# ESP32.net
KiCad netlist of a schematic drawn in Altium Designer
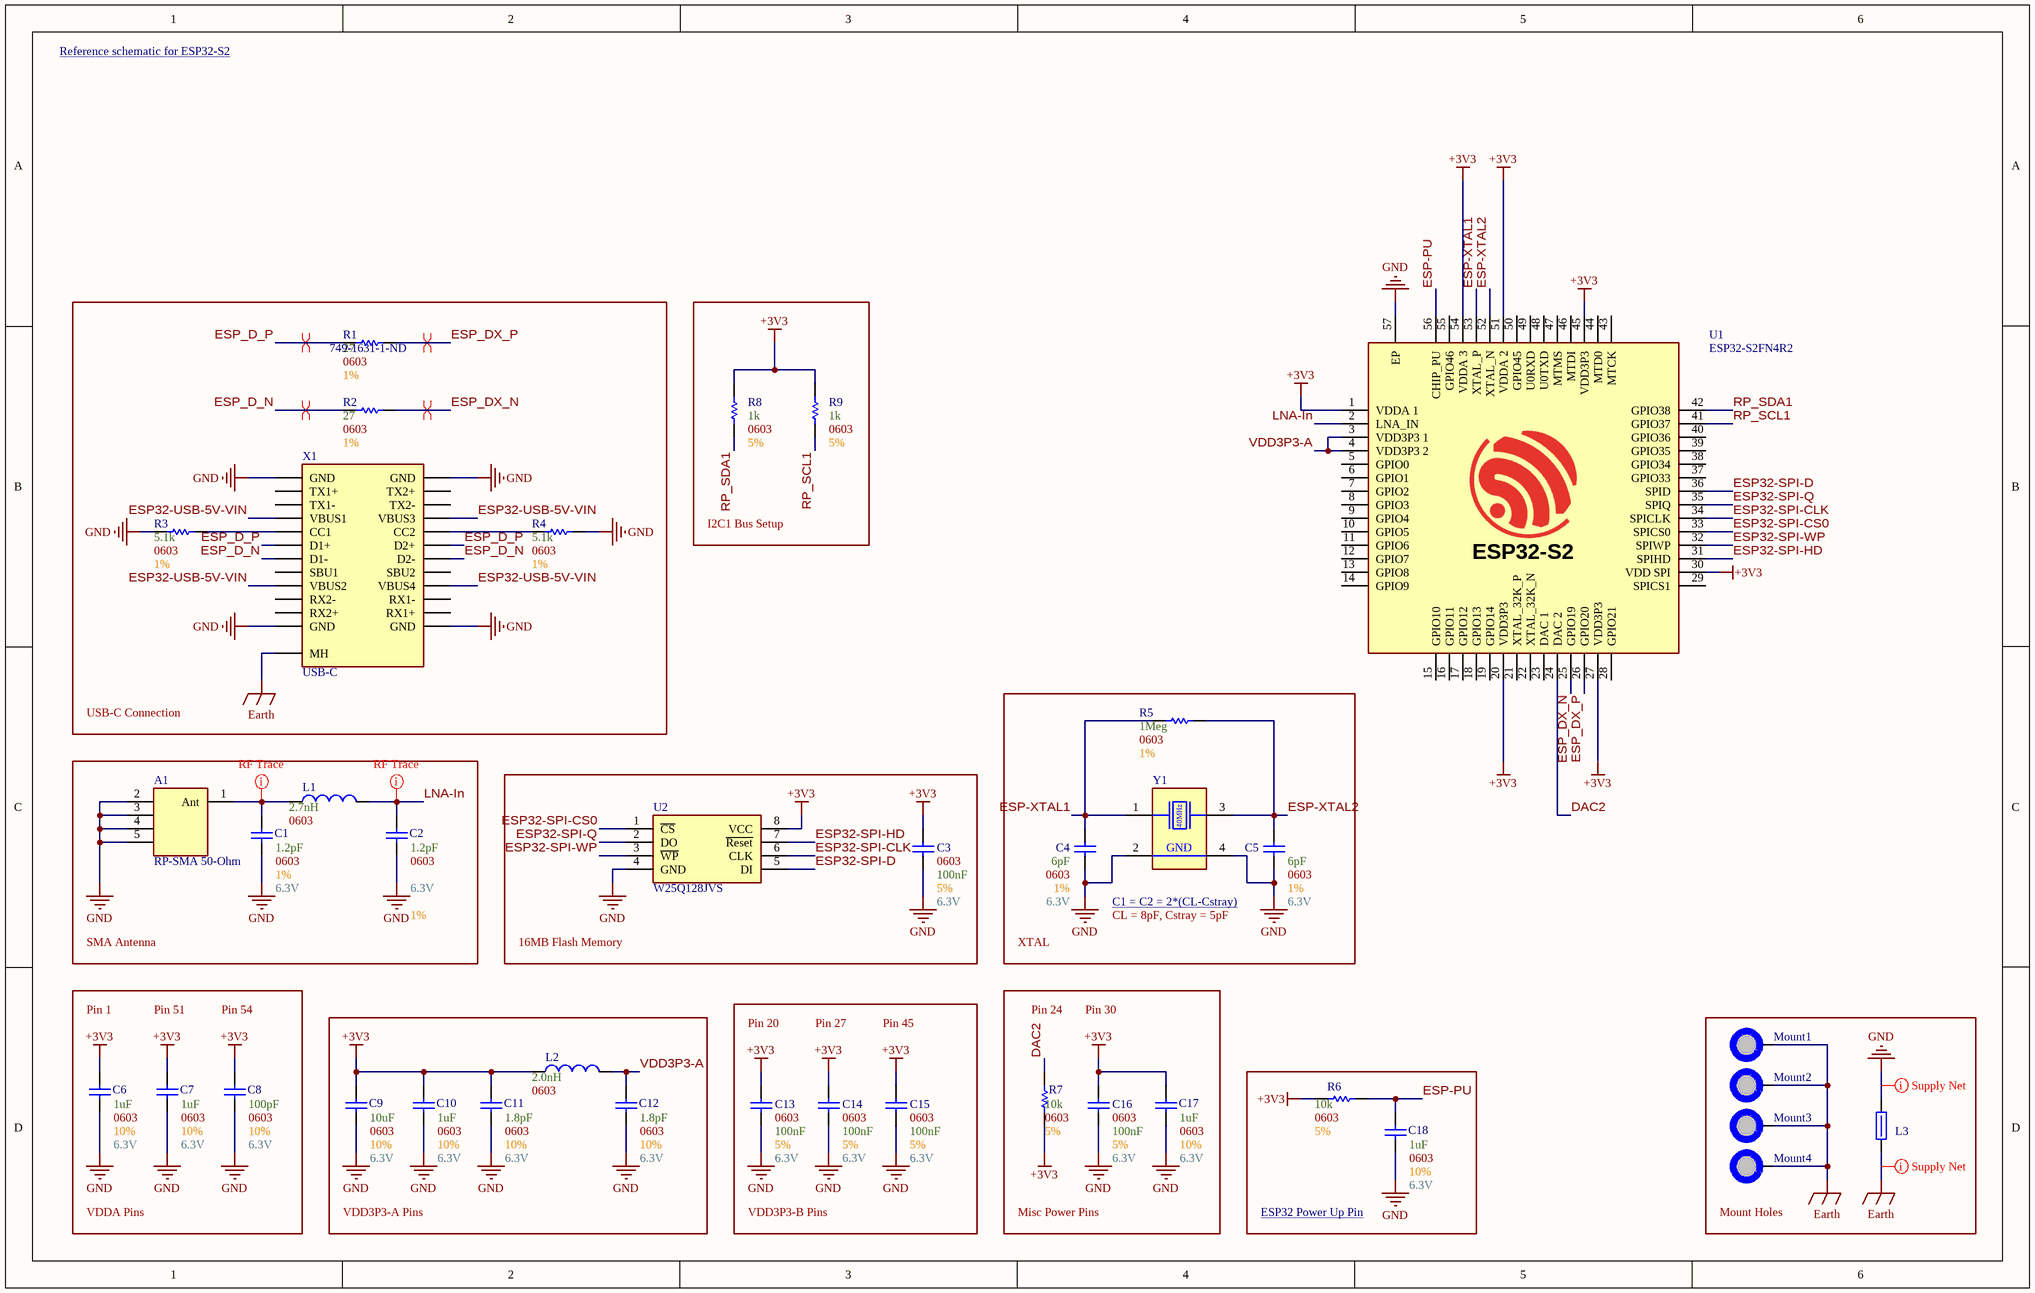
[diagram p0: ESP32.SchDoc]

(export (version "E")
  (design (tool "Eeschema 10.0.6"))
  (components
    (comp (ref "A1")
      (value "RP-SMA 50-Ohm")
      (footprint "[SMA] RP-SMA 90deg Jack")
      (description "PCB.RPSMAFRA.HT")
      (libsource (lib "RADM Connectors") (part "[SMA] RP-SMA 90deg Jack"))
    )
    (comp (ref "C1")
      (value "SMD Nonpolarized")
      (footprint "[Cap] SMD 0603")
      (fields
        (field (name "VOLTAGE") "6.3V")
        (field (name "TOLERANCE") "1%")
        (field (name "SIZE PACKAGE") "0603")
        (field (name "CAPACITANCE") "1.2pF")
      )
      (libsource (lib "RADM Components") (part "[Cap] SMD Nonpolarized"))
    )
    (comp (ref "C2")
      (value "SMD Nonpolarized")
      (footprint "[Cap] SMD 0603")
      (fields
        (field (name "VOLTAGE") "6.3V")
        (field (name "TOLERANCE") "1%")
        (field (name "SIZE PACKAGE") "0603")
        (field (name "CAPACITANCE") "1.2pF")
      )
      (libsource (lib "RADM Components") (part "[Cap] SMD Nonpolarized"))
    )
    (comp (ref "C3")
      (value "[Cap] SMD Nonpolarized")
      (footprint "[Cap] SMD 0603")
      (fields
        (field (name "SIZE PACKAGE") "0603")
        (field (name "CAPACITANCE") "100nF")
        (field (name "VOLTAGE") "6.3V")
        (field (name "TOLERANCE") "5%")
      )
      (libsource (lib "RADM Components") (part "[Cap] SMD Nonpolarized"))
    )
    (comp (ref "C4")
      (value "SMD Nonpolarized")
      (footprint "[Cap] SMD 0603")
      (fields
        (field (name "VOLTAGE") "6.3V")
        (field (name "TOLERANCE") "1%")
        (field (name "SIZE PACKAGE") "0603")
        (field (name "CAPACITANCE") "6pF")
      )
      (libsource (lib "RADM Components") (part "[Cap] SMD Nonpolarized"))
    )
    (comp (ref "C5")
      (value "SMD Nonpolarized")
      (footprint "[Cap] SMD 0603")
      (fields
        (field (name "VOLTAGE") "6.3V")
        (field (name "TOLERANCE") "1%")
        (field (name "SIZE PACKAGE") "0603")
        (field (name "CAPACITANCE") "6pF")
      )
      (libsource (lib "RADM Components") (part "[Cap] SMD Nonpolarized"))
    )
    (comp (ref "C6")
      (value "SMD Nonpolarized")
      (footprint "[Cap] SMD 0603")
      (fields
        (field (name "VOLTAGE") "6.3V")
        (field (name "TOLERANCE") "10%")
        (field (name "SIZE PACKAGE") "0603")
        (field (name "CAPACITANCE") "1uF")
      )
      (libsource (lib "RADM Components") (part "[Cap] SMD Nonpolarized"))
    )
    (comp (ref "C7")
      (value "SMD Nonpolarized")
      (footprint "[Cap] SMD 0603")
      (fields
        (field (name "VOLTAGE") "6.3V")
        (field (name "TOLERANCE") "10%")
        (field (name "SIZE PACKAGE") "0603")
        (field (name "CAPACITANCE") "1uF")
      )
      (libsource (lib "RADM Components") (part "[Cap] SMD Nonpolarized"))
    )
    (comp (ref "C8")
      (value "SMD Nonpolarized")
      (footprint "[Cap] SMD 0603")
      (fields
        (field (name "VOLTAGE") "6.3V")
        (field (name "TOLERANCE") "10%")
        (field (name "SIZE PACKAGE") "0603")
        (field (name "CAPACITANCE") "100pF")
      )
      (libsource (lib "RADM Components") (part "[Cap] SMD Nonpolarized"))
    )
    (comp (ref "C9")
      (value "SMD Nonpolarized")
      (footprint "[Cap] SMD 0603")
      (fields
        (field (name "VOLTAGE") "6.3V")
        (field (name "TOLERANCE") "10%")
        (field (name "SIZE PACKAGE") "0603")
        (field (name "CAPACITANCE") "10uF")
      )
      (libsource (lib "RADM Components") (part "[Cap] SMD Nonpolarized"))
    )
    (comp (ref "C10")
      (value "SMD Nonpolarized")
      (footprint "[Cap] SMD 0603")
      (fields
        (field (name "VOLTAGE") "6.3V")
        (field (name "TOLERANCE") "10%")
        (field (name "SIZE PACKAGE") "0603")
        (field (name "CAPACITANCE") "1uF")
      )
      (libsource (lib "RADM Components") (part "[Cap] SMD Nonpolarized"))
    )
    (comp (ref "C11")
      (value "SMD Nonpolarized")
      (footprint "[Cap] SMD 0603")
      (fields
        (field (name "VOLTAGE") "6.3V")
        (field (name "TOLERANCE") "10%")
        (field (name "SIZE PACKAGE") "0603")
        (field (name "CAPACITANCE") "1.8pF")
      )
      (libsource (lib "RADM Components") (part "[Cap] SMD Nonpolarized"))
    )
    (comp (ref "C12")
      (value "SMD Nonpolarized")
      (footprint "[Cap] SMD 0603")
      (fields
        (field (name "VOLTAGE") "6.3V")
        (field (name "TOLERANCE") "10%")
        (field (name "SIZE PACKAGE") "0603")
        (field (name "CAPACITANCE") "1.8pF")
      )
      (libsource (lib "RADM Components") (part "[Cap] SMD Nonpolarized"))
    )
    (comp (ref "C13")
      (value "[Cap] SMD Nonpolarized")
      (footprint "[Cap] SMD 0603")
      (fields
        (field (name "SIZE PACKAGE") "0603")
        (field (name "CAPACITANCE") "100nF")
        (field (name "VOLTAGE") "6.3V")
        (field (name "TOLERANCE") "5%")
      )
      (libsource (lib "RADM Components") (part "[Cap] SMD Nonpolarized"))
    )
    (comp (ref "C14")
      (value "[Cap] SMD Nonpolarized")
      (footprint "[Cap] SMD 0603")
      (fields
        (field (name "SIZE PACKAGE") "0603")
        (field (name "CAPACITANCE") "100nF")
        (field (name "VOLTAGE") "6.3V")
        (field (name "TOLERANCE") "5%")
      )
      (libsource (lib "RADM Components") (part "[Cap] SMD Nonpolarized"))
    )
    (comp (ref "C15")
      (value "[Cap] SMD Nonpolarized")
      (footprint "[Cap] SMD 0603")
      (fields
        (field (name "SIZE PACKAGE") "0603")
        (field (name "CAPACITANCE") "100nF")
        (field (name "VOLTAGE") "6.3V")
        (field (name "TOLERANCE") "5%")
      )
      (libsource (lib "RADM Components") (part "[Cap] SMD Nonpolarized"))
    )
    (comp (ref "C16")
      (value "[Cap] SMD Nonpolarized")
      (footprint "[Cap] SMD 0603")
      (fields
        (field (name "SIZE PACKAGE") "0603")
        (field (name "CAPACITANCE") "100nF")
        (field (name "VOLTAGE") "6.3V")
        (field (name "TOLERANCE") "5%")
      )
      (libsource (lib "RADM Components") (part "[Cap] SMD Nonpolarized"))
    )
    (comp (ref "C17")
      (value "SMD Nonpolarized")
      (footprint "[Cap] SMD 0603")
      (fields
        (field (name "VOLTAGE") "6.3V")
        (field (name "TOLERANCE") "10%")
        (field (name "SIZE PACKAGE") "0603")
        (field (name "CAPACITANCE") "1uF")
      )
      (libsource (lib "RADM Components") (part "[Cap] SMD Nonpolarized"))
    )
    (comp (ref "C18")
      (value "SMD Nonpolarized")
      (footprint "[Cap] SMD 0603")
      (fields
        (field (name "VOLTAGE") "6.3V")
        (field (name "TOLERANCE") "10%")
        (field (name "SIZE PACKAGE") "0603")
        (field (name "CAPACITANCE") "1uF")
      )
      (libsource (lib "RADM Components") (part "[Cap] SMD Nonpolarized"))
    )
    (comp (ref "L1")
      (value "SMD Inductor")
      (footprint "[Inductor] SMD 0603")
      (fields (field (name "SIZE PACKAGE") "0603") (field (name "INDUCTANCE") "2.7nH"))
      (libsource (lib "RADM Components") (part "[Inductor] SMD Inductor"))
    )
    (comp (ref "L2")
      (value "SMD Inductor")
      (footprint "[Inductor] SMD 0603")
      (fields (field (name "SIZE PACKAGE") "0603") (field (name "INDUCTANCE") "2.0nH"))
      (libsource (lib "RADM Components") (part "[Inductor] SMD Inductor"))
    )
    (comp (ref "L3")
      (value "652-MH2029-300Y")
      (footprint "[Ferrite] SMD Bead 0805 (1)")
      (libsource (lib "RADM Components") (part "[Ferrite] SMD Ferrite Bead (1)"))
    )
    (comp (ref "Mount1")
      (value "M3 Mount Hole")
      (footprint "[Mount] M3 Mount Hole")
      (description "Place at least 4.5mm from board edge. Plated.")
      (libsource (lib "RADM Connectors") (part "[Mount] M3 Mount Hole"))
    )
    (comp (ref "Mount2")
      (value "M3 Mount Hole")
      (footprint "[Mount] M3 Mount Hole")
      (description "Place at least 4.5mm from board edge. Plated.")
      (libsource (lib "RADM Connectors") (part "[Mount] M3 Mount Hole"))
    )
    (comp (ref "Mount3")
      (value "M3 Mount Hole")
      (footprint "[Mount] M3 Mount Hole")
      (description "Place at least 4.5mm from board edge. Plated.")
      (libsource (lib "RADM Connectors") (part "[Mount] M3 Mount Hole"))
    )
    (comp (ref "Mount4")
      (value "M3 Mount Hole")
      (footprint "[Mount] M3 Mount Hole")
      (description "Place at least 4.5mm from board edge. Plated.")
      (libsource (lib "RADM Connectors") (part "[Mount] M3 Mount Hole"))
    )
    (comp (ref "R1")
      (value "[Res] SMD Resistor")
      (footprint "[Res] SMD 0603")
      (description "Generic")
      (fields
        (field (name "TOLERANCE") "1%")
        (field (name "RESISTANCE") "27")
        (field (name "SIZE PACKAGE") "0603")
        (field (name "SUPPLIER PART NUMBER 1") "749-1631-1-ND")
      )
      (libsource (lib "RADM Components") (part "[Res] SMD Resistor"))
    )
    (comp (ref "R2")
      (value "[Res] SMD Resistor")
      (footprint "[Res] SMD 0603")
      (description "Generic")
      (fields
        (field (name "TOLERANCE") "1%")
        (field (name "RESISTANCE") "27")
        (field (name "SIZE PACKAGE") "0603")
      )
      (libsource (lib "RADM Components") (part "[Res] SMD Resistor"))
    )
    (comp (ref "R3")
      (value "[Res] SMD Resistor")
      (footprint "[Res] SMD 0603")
      (description "Generic")
      (fields
        (field (name "TOLERANCE") "1%")
        (field (name "RESISTANCE") "5.1k")
        (field (name "SIZE PACKAGE") "0603")
      )
      (libsource (lib "RADM Components") (part "[Res] SMD Resistor"))
    )
    (comp (ref "R4")
      (value "[Res] SMD Resistor")
      (footprint "[Res] SMD 0603")
      (description "Generic")
      (fields
        (field (name "TOLERANCE") "1%")
        (field (name "RESISTANCE") "5.1k")
        (field (name "SIZE PACKAGE") "0603")
      )
      (libsource (lib "RADM Components") (part "[Res] SMD Resistor"))
    )
    (comp (ref "R5")
      (value "[Res] SMD Resistor")
      (footprint "[Res] SMD 0603")
      (description "Generic")
      (fields
        (field (name "TOLERANCE") "1%")
        (field (name "RESISTANCE") "1Meg")
        (field (name "SIZE PACKAGE") "0603")
      )
      (libsource (lib "RADM Components") (part "[Res] SMD Resistor"))
    )
    (comp (ref "R6")
      (value "[Res] SMD Resistor")
      (footprint "[Res] SMD 0603")
      (description "Generic")
      (fields
        (field (name "TOLERANCE") "5%")
        (field (name "RESISTANCE") "10k")
        (field (name "SIZE PACKAGE") "0603")
      )
      (libsource (lib "RADM Components") (part "[Res] SMD Resistor"))
    )
    (comp (ref "R7")
      (value "[Res] SMD Resistor")
      (footprint "[Res] SMD 0603")
      (description "Generic")
      (fields
        (field (name "TOLERANCE") "5%")
        (field (name "RESISTANCE") "10k")
        (field (name "SIZE PACKAGE") "0603")
      )
      (libsource (lib "RADM Components") (part "[Res] SMD Resistor"))
    )
    (comp (ref "R8")
      (value "[Res] SMD Resistor")
      (footprint "[Res] SMD 0603")
      (description "Generic")
      (fields
        (field (name "RESISTANCE") "1k")
        (field (name "SIZE PACKAGE") "0603")
        (field (name "TOLERANCE") "5%")
      )
      (libsource (lib "RADM Components") (part "[Res] SMD Resistor"))
    )
    (comp (ref "R9")
      (value "[Res] SMD Resistor")
      (footprint "[Res] SMD 0603")
      (description "Generic")
      (fields
        (field (name "RESISTANCE") "1k")
        (field (name "SIZE PACKAGE") "0603")
        (field (name "TOLERANCE") "5%")
      )
      (libsource (lib "RADM Components") (part "[Res] SMD Resistor"))
    )
    (comp (ref "U1")
      (value "ESP32-S2FN4R2")
      (footprint "[MCU] ESP32-S2")
      (libsource (lib "RADM Components") (part "[MCU] ESP32-S2"))
    )
    (comp (ref "U2")
      (value "W25Q128JVS")
      (footprint "[Mem] 16Mb Flash Memory")
      (description "W25Q128JVSIQ TR")
      (libsource (lib "RADM Components") (part "[Mem] 16Mb Flash Memory"))
    )
    (comp (ref "X1")
      (value "USB-C")
      (footprint "[Port] USB-C")
      (libsource (lib "RADM Connectors") (part "[Port] USB Type-C"))
    )
    (comp (ref "Y1")
      (value "40MHz Crystal")
      (footprint "[XTAL] SMD 40MHz")
      (description "CX2016DB40000D0FLJCC")
      (libsource (lib "RADM Components") (part "[XTAL] SMD 40MHz"))
    )
  )
  (nets
    (net (code "1") (name "+3V3") (class "Default")
      (node (ref "C10") (pin "2") (pinfunction "2_2") (pintype "passive"))
      (node (ref "C11") (pin "2") (pinfunction "2_2") (pintype "passive"))
      (node (ref "C13") (pin "2") (pinfunction "2_2") (pintype "passive"))
      (node (ref "C14") (pin "2") (pinfunction "2_2") (pintype "passive"))
      (node (ref "C15") (pin "2") (pinfunction "2_2") (pintype "passive"))
      (node (ref "C16") (pin "2") (pinfunction "2_2") (pintype "passive"))
      (node (ref "C17") (pin "2") (pinfunction "2_2") (pintype "passive"))
      (node (ref "C3") (pin "2") (pinfunction "2_2") (pintype "passive"))
      (node (ref "C6") (pin "2") (pinfunction "2_2") (pintype "passive"))
      (node (ref "C7") (pin "2") (pinfunction "2_2") (pintype "passive"))
      (node (ref "C8") (pin "2") (pinfunction "2_2") (pintype "passive"))
      (node (ref "C9") (pin "2") (pinfunction "2_2") (pintype "passive"))
      (node (ref "L2") (pin "1") (pinfunction "1_1") (pintype "passive"))
      (node (ref "R6") (pin "1") (pinfunction "1_1") (pintype "passive"))
      (node (ref "R7") (pin "1") (pinfunction "1_1") (pintype "passive"))
      (node (ref "R8") (pin "2") (pinfunction "2_2") (pintype "passive"))
      (node (ref "R9") (pin "2") (pinfunction "2_2") (pintype "passive"))
      (node (ref "U1") (pin "1") (pinfunction "VDDA_1_1") (pintype "passive"))
      (node (ref "U1") (pin "20") (pinfunction "VDD3P3_20") (pintype "passive"))
      (node (ref "U1") (pin "27") (pinfunction "VDD3P3_27") (pintype "passive"))
      (node (ref "U1") (pin "30") (pinfunction "VDD_SPI_30") (pintype "passive"))
      (node (ref "U1") (pin "45") (pinfunction "VDD3P3_45") (pintype "passive"))
      (node (ref "U1") (pin "51") (pinfunction "VDDA_2_51") (pintype "passive"))
      (node (ref "U1") (pin "54") (pinfunction "VDDA_3_54") (pintype "passive"))
      (node (ref "U2") (pin "8") (pinfunction "VCC_8") (pintype "passive"))
    )
    (net (code "2") (name "/DAC2") (class "Default")
      (node (ref "R7") (pin "2") (pinfunction "2_2") (pintype "passive"))
      (node (ref "U1") (pin "24") (pinfunction "DAC_2_24") (pintype "passive"))
    )
    (net (code "3") (name "/ESP-PU") (class "Default")
      (node (ref "C18") (pin "2") (pinfunction "2_2") (pintype "passive"))
      (node (ref "R6") (pin "2") (pinfunction "2_2") (pintype "passive"))
      (node (ref "U1") (pin "56") (pinfunction "CHIP_PU_56") (pintype "passive"))
    )
    (net (code "4") (name "/ESP-XTAL1") (class "Default")
      (node (ref "C4") (pin "2") (pinfunction "2_2") (pintype "passive"))
      (node (ref "R5") (pin "2") (pinfunction "2_2") (pintype "passive"))
      (node (ref "U1") (pin "53") (pinfunction "XTAL_P_53") (pintype "passive"))
      (node (ref "Y1") (pin "1") (pinfunction "XTAL1_1") (pintype "power_in"))
    )
    (net (code "5") (name "/ESP-XTAL2") (class "Default")
      (node (ref "C5") (pin "2") (pinfunction "2_2") (pintype "passive"))
      (node (ref "R5") (pin "1") (pinfunction "1_1") (pintype "passive"))
      (node (ref "U1") (pin "52") (pinfunction "XTAL_N_52") (pintype "passive"))
      (node (ref "Y1") (pin "3") (pinfunction "XTAL2_3") (pintype "power_in"))
    )
    (net (code "6") (name "/ESP32-SPI-CLK") (class "Default")
      (node (ref "U1") (pin "34") (pinfunction "SPICLK_34") (pintype "passive"))
      (node (ref "U2") (pin "6") (pinfunction "CLK_6") (pintype "passive"))
    )
    (net (code "7") (name "/ESP32-SPI-CS0") (class "Default")
      (node (ref "U1") (pin "33") (pinfunction "SPICS0_33") (pintype "passive"))
      (node (ref "U2") (pin "1") (pinfunction "~{CS}_1") (pintype "passive"))
    )
    (net (code "8") (name "/ESP32-SPI-D") (class "Default")
      (node (ref "U1") (pin "36") (pinfunction "SPID_36") (pintype "passive"))
      (node (ref "U2") (pin "5") (pinfunction "DI_5") (pintype "passive"))
    )
    (net (code "9") (name "/ESP32-SPI-HD") (class "Default")
      (node (ref "U1") (pin "31") (pinfunction "SPIHD_31") (pintype "passive"))
      (node (ref "U2") (pin "7") (pinfunction "~{Reset}_7") (pintype "passive"))
    )
    (net (code "10") (name "/ESP32-SPI-Q") (class "Default")
      (node (ref "U1") (pin "35") (pinfunction "SPIQ_35") (pintype "passive"))
      (node (ref "U2") (pin "2") (pinfunction "DO_2") (pintype "passive"))
    )
    (net (code "11") (name "/ESP32-SPI-WP") (class "Default")
      (node (ref "U1") (pin "32") (pinfunction "SPIWP_32") (pintype "passive"))
      (node (ref "U2") (pin "3") (pinfunction "~{WP}_3") (pintype "passive"))
    )
    (net (code "12") (name "/ESP32-USB-5V-VIN") (class "Default")
      (node (ref "X1") (pin "A4") (pinfunction "VBUS1_A4") (pintype "passive"))
      (node (ref "X1") (pin "A9") (pinfunction "VBUS2_A9") (pintype "passive"))
      (node (ref "X1") (pin "B4") (pinfunction "VBUS3_B4") (pintype "passive"))
      (node (ref "X1") (pin "B9") (pinfunction "VBUS4_B9") (pintype "passive"))
    )
    (net (code "13") (name "/ESP_DX_N") (class "Default")
      (node (ref "R2") (pin "2") (pinfunction "2_2") (pintype "passive"))
      (node (ref "U1") (pin "25") (pinfunction "GPIO19_25") (pintype "passive"))
    )
    (net (code "14") (name "/ESP_DX_P") (class "Default")
      (node (ref "R1") (pin "2") (pinfunction "2_2") (pintype "passive"))
      (node (ref "U1") (pin "26") (pinfunction "GPIO20_26") (pintype "passive"))
    )
    (net (code "15") (name "/ESP_D_N") (class "Default")
      (node (ref "R2") (pin "1") (pinfunction "1_1") (pintype "passive"))
      (node (ref "X1") (pin "A7") (pinfunction "D1-_A7") (pintype "passive"))
      (node (ref "X1") (pin "B7") (pinfunction "D2-_B7") (pintype "passive"))
    )
    (net (code "16") (name "/ESP_D_P") (class "Default")
      (node (ref "R1") (pin "1") (pinfunction "1_1") (pintype "passive"))
      (node (ref "X1") (pin "A6") (pinfunction "D1+_A6") (pintype "passive"))
      (node (ref "X1") (pin "B6") (pinfunction "D2+_B6") (pintype "passive"))
    )
    (net (code "17") (name "/LNA-In") (class "Default")
      (node (ref "C2") (pin "2") (pinfunction "2_2") (pintype "passive"))
      (node (ref "L1") (pin "2") (pinfunction "2_2") (pintype "passive"))
      (node (ref "U1") (pin "2") (pinfunction "LNA_IN_2") (pintype "passive"))
    )
    (net (code "18") (name "/RP_SCL1") (class "Default")
      (node (ref "R9") (pin "1") (pinfunction "1_1") (pintype "passive"))
      (node (ref "U1") (pin "41") (pinfunction "GPIO37_41") (pintype "passive"))
    )
    (net (code "19") (name "/RP_SDA1") (class "Default")
      (node (ref "R8") (pin "1") (pinfunction "1_1") (pintype "passive"))
      (node (ref "U1") (pin "42") (pinfunction "GPIO38_42") (pintype "passive"))
    )
    (net (code "20") (name "/VDD3P3-A") (class "Default")
      (node (ref "C12") (pin "2") (pinfunction "2_2") (pintype "passive"))
      (node (ref "L2") (pin "2") (pinfunction "2_2") (pintype "passive"))
      (node (ref "U1") (pin "3") (pinfunction "VDD3P3_1_3") (pintype "passive"))
      (node (ref "U1") (pin "4") (pinfunction "VDD3P3_2_4") (pintype "passive"))
    )
    (net (code "21") (name "Earth") (class "Default")
      (node (ref "L3") (pin "1") (pinfunction "1_1") (pintype "passive"))
      (node (ref "Mount1") (pin "1") (pintype "power_in"))
      (node (ref "Mount2") (pin "1") (pintype "power_in"))
      (node (ref "Mount3") (pin "1") (pintype "power_in"))
      (node (ref "Mount4") (pin "1") (pintype "power_in"))
      (node (ref "X1") (pin "MH") (pinfunction "MH_MH") (pintype "passive"))
    )
    (net (code "22") (name "GND") (class "Default")
      (node (ref "A1") (pin "2") (pinfunction "2_2") (pintype "passive"))
      (node (ref "A1") (pin "3") (pinfunction "3_3") (pintype "passive"))
      (node (ref "A1") (pin "4") (pinfunction "4_4") (pintype "passive"))
      (node (ref "A1") (pin "5") (pinfunction "5_5") (pintype "passive"))
      (node (ref "C1") (pin "1") (pinfunction "1_1") (pintype "passive"))
      (node (ref "C10") (pin "1") (pinfunction "1_1") (pintype "passive"))
      (node (ref "C11") (pin "1") (pinfunction "1_1") (pintype "passive"))
      (node (ref "C12") (pin "1") (pinfunction "1_1") (pintype "passive"))
      (node (ref "C13") (pin "1") (pinfunction "1_1") (pintype "passive"))
      (node (ref "C14") (pin "1") (pinfunction "1_1") (pintype "passive"))
      (node (ref "C15") (pin "1") (pinfunction "1_1") (pintype "passive"))
      (node (ref "C16") (pin "1") (pinfunction "1_1") (pintype "passive"))
      (node (ref "C17") (pin "1") (pinfunction "1_1") (pintype "passive"))
      (node (ref "C18") (pin "1") (pinfunction "1_1") (pintype "passive"))
      (node (ref "C2") (pin "1") (pinfunction "1_1") (pintype "passive"))
      (node (ref "C3") (pin "1") (pinfunction "1_1") (pintype "passive"))
      (node (ref "C4") (pin "1") (pinfunction "1_1") (pintype "passive"))
      (node (ref "C5") (pin "1") (pinfunction "1_1") (pintype "passive"))
      (node (ref "C6") (pin "1") (pinfunction "1_1") (pintype "passive"))
      (node (ref "C7") (pin "1") (pinfunction "1_1") (pintype "passive"))
      (node (ref "C8") (pin "1") (pinfunction "1_1") (pintype "passive"))
      (node (ref "C9") (pin "1") (pinfunction "1_1") (pintype "passive"))
      (node (ref "L3") (pin "2") (pinfunction "2_2") (pintype "passive"))
      (node (ref "R3") (pin "1") (pinfunction "1_1") (pintype "passive"))
      (node (ref "R4") (pin "2") (pinfunction "2_2") (pintype "passive"))
      (node (ref "U1") (pin "57") (pinfunction "EP_57") (pintype "passive"))
      (node (ref "U2") (pin "4") (pinfunction "GND_4") (pintype "passive"))
      (node (ref "X1") (pin "A1") (pinfunction "GND_A1") (pintype "passive"))
      (node (ref "X1") (pin "A12") (pinfunction "GND_A12") (pintype "passive"))
      (node (ref "X1") (pin "B1") (pinfunction "GND_B1") (pintype "passive"))
      (node (ref "X1") (pin "B12") (pinfunction "GND_B12") (pintype "passive"))
      (node (ref "Y1") (pin "2") (pinfunction "GND_2") (pintype "power_in"))
      (node (ref "Y1") (pin "4") (pinfunction "GND_4") (pintype "power_in"))
    )
    (net (code "23") (name "Net-(A1-Ant)") (class "Default")
      (node (ref "A1") (pin "1") (pinfunction "Ant_1") (pintype "passive"))
      (node (ref "C1") (pin "2") (pinfunction "2_2") (pintype "passive"))
      (node (ref "L1") (pin "1") (pinfunction "1_1") (pintype "passive"))
    )
    (net (code "24") (name "Net-(X1-CC1)") (class "Default")
      (node (ref "R3") (pin "2") (pinfunction "2_2") (pintype "passive"))
      (node (ref "X1") (pin "A5") (pinfunction "CC1_A5") (pintype "passive"))
    )
    (net (code "25") (name "Net-(X1-CC2)") (class "Default")
      (node (ref "R4") (pin "1") (pinfunction "1_1") (pintype "passive"))
      (node (ref "X1") (pin "B5") (pinfunction "CC2_B5") (pintype "passive"))
    )
    (net (code "26") (name "unconnected-(U1-DAC_1-Pad23)") (class "Default")
      (node (ref "U1") (pin "23") (pinfunction "DAC_1_23") (pintype "passive"))
    )
    (net (code "27") (name "unconnected-(U1-GPIO0-Pad5)") (class "Default")
      (node (ref "U1") (pin "5") (pinfunction "GPIO0_5") (pintype "passive"))
    )
    (net (code "28") (name "unconnected-(U1-GPIO1-Pad6)") (class "Default")
      (node (ref "U1") (pin "6") (pinfunction "GPIO1_6") (pintype "passive"))
    )
    (net (code "29") (name "unconnected-(U1-GPIO2-Pad7)") (class "Default")
      (node (ref "U1") (pin "7") (pinfunction "GPIO2_7") (pintype "passive"))
    )
    (net (code "30") (name "unconnected-(U1-GPIO3-Pad8)") (class "Default")
      (node (ref "U1") (pin "8") (pinfunction "GPIO3_8") (pintype "passive"))
    )
    (net (code "31") (name "unconnected-(U1-GPIO4-Pad9)") (class "Default")
      (node (ref "U1") (pin "9") (pinfunction "GPIO4_9") (pintype "passive"))
    )
    (net (code "32") (name "unconnected-(U1-GPIO5-Pad10)") (class "Default")
      (node (ref "U1") (pin "10") (pinfunction "GPIO5_10") (pintype "passive"))
    )
    (net (code "33") (name "unconnected-(U1-GPIO6-Pad11)") (class "Default")
      (node (ref "U1") (pin "11") (pinfunction "GPIO6_11") (pintype "passive"))
    )
    (net (code "34") (name "unconnected-(U1-GPIO7-Pad12)") (class "Default")
      (node (ref "U1") (pin "12") (pinfunction "GPIO7_12") (pintype "passive"))
    )
    (net (code "35") (name "unconnected-(U1-GPIO8-Pad13)") (class "Default")
      (node (ref "U1") (pin "13") (pinfunction "GPIO8_13") (pintype "passive"))
    )
    (net (code "36") (name "unconnected-(U1-GPIO9-Pad14)") (class "Default")
      (node (ref "U1") (pin "14") (pinfunction "GPIO9_14") (pintype "passive"))
    )
    (net (code "37") (name "unconnected-(U1-GPIO10-Pad15)") (class "Default")
      (node (ref "U1") (pin "15") (pinfunction "GPIO10_15") (pintype "passive"))
    )
    (net (code "38") (name "unconnected-(U1-GPIO11-Pad16)") (class "Default")
      (node (ref "U1") (pin "16") (pinfunction "GPIO11_16") (pintype "passive"))
    )
    (net (code "39") (name "unconnected-(U1-GPIO12-Pad17)") (class "Default")
      (node (ref "U1") (pin "17") (pinfunction "GPIO12_17") (pintype "passive"))
    )
    (net (code "40") (name "unconnected-(U1-GPIO13-Pad18)") (class "Default")
      (node (ref "U1") (pin "18") (pinfunction "GPIO13_18") (pintype "passive"))
    )
    (net (code "41") (name "unconnected-(U1-GPIO14-Pad19)") (class "Default")
      (node (ref "U1") (pin "19") (pinfunction "GPIO14_19") (pintype "passive"))
    )
    (net (code "42") (name "unconnected-(U1-GPIO21-Pad28)") (class "Default")
      (node (ref "U1") (pin "28") (pinfunction "GPIO21_28") (pintype "passive"))
    )
    (net (code "43") (name "unconnected-(U1-GPIO33-Pad37)") (class "Default")
      (node (ref "U1") (pin "37") (pinfunction "GPIO33_37") (pintype "passive"))
    )
    (net (code "44") (name "unconnected-(U1-GPIO34-Pad38)") (class "Default")
      (node (ref "U1") (pin "38") (pinfunction "GPIO34_38") (pintype "passive"))
    )
    (net (code "45") (name "unconnected-(U1-GPIO35-Pad39)") (class "Default")
      (node (ref "U1") (pin "39") (pinfunction "GPIO35_39") (pintype "passive"))
    )
    (net (code "46") (name "unconnected-(U1-GPIO36-Pad40)") (class "Default")
      (node (ref "U1") (pin "40") (pinfunction "GPIO36_40") (pintype "passive"))
    )
    (net (code "47") (name "unconnected-(U1-GPIO45-Pad50)") (class "Default")
      (node (ref "U1") (pin "50") (pinfunction "GPIO45_50") (pintype "passive"))
    )
    (net (code "48") (name "unconnected-(U1-GPIO46-Pad55)") (class "Default")
      (node (ref "U1") (pin "55") (pinfunction "GPIO46_55") (pintype "passive"))
    )
    (net (code "49") (name "unconnected-(U1-MTCK-Pad43)") (class "Default")
      (node (ref "U1") (pin "43") (pinfunction "MTCK_43") (pintype "passive"))
    )
    (net (code "50") (name "unconnected-(U1-MTD0-Pad44)") (class "Default")
      (node (ref "U1") (pin "44") (pinfunction "MTD0_44") (pintype "passive"))
    )
    (net (code "51") (name "unconnected-(U1-MTDI-Pad46)") (class "Default")
      (node (ref "U1") (pin "46") (pinfunction "MTDI_46") (pintype "passive"))
    )
    (net (code "52") (name "unconnected-(U1-MTMS-Pad47)") (class "Default")
      (node (ref "U1") (pin "47") (pinfunction "MTMS_47") (pintype "passive"))
    )
    (net (code "53") (name "unconnected-(U1-SPICS1-Pad29)") (class "Default")
      (node (ref "U1") (pin "29") (pinfunction "SPICS1_29") (pintype "passive"))
    )
    (net (code "54") (name "unconnected-(U1-U0RXD-Pad49)") (class "Default")
      (node (ref "U1") (pin "49") (pinfunction "U0RXD_49") (pintype "passive"))
    )
    (net (code "55") (name "unconnected-(U1-U0TXD-Pad48)") (class "Default")
      (node (ref "U1") (pin "48") (pinfunction "U0TXD_48") (pintype "passive"))
    )
    (net (code "56") (name "unconnected-(U1-XTAL_32K_N-Pad22)") (class "Default")
      (node (ref "U1") (pin "22") (pinfunction "XTAL_32K_N_22") (pintype "passive"))
    )
    (net (code "57") (name "unconnected-(U1-XTAL_32K_P-Pad21)") (class "Default")
      (node (ref "U1") (pin "21") (pinfunction "XTAL_32K_P_21") (pintype "passive"))
    )
    (net (code "58") (name "unconnected-(X1-RX1+-PadB11)") (class "Default")
      (node (ref "X1") (pin "B11") (pinfunction "RX1+_B11") (pintype "passive"))
    )
    (net (code "59") (name "unconnected-(X1-RX1--PadB10)") (class "Default")
      (node (ref "X1") (pin "B10") (pinfunction "RX1-_B10") (pintype "passive"))
    )
    (net (code "60") (name "unconnected-(X1-RX2+-PadA11)") (class "Default")
      (node (ref "X1") (pin "A11") (pinfunction "RX2+_A11") (pintype "passive"))
    )
    (net (code "61") (name "unconnected-(X1-RX2--PadA10)") (class "Default")
      (node (ref "X1") (pin "A10") (pinfunction "RX2-_A10") (pintype "passive"))
    )
    (net (code "62") (name "unconnected-(X1-SBU1-PadA8)") (class "Default")
      (node (ref "X1") (pin "A8") (pinfunction "SBU1_A8") (pintype "passive"))
    )
    (net (code "63") (name "unconnected-(X1-SBU2-PadB8)") (class "Default")
      (node (ref "X1") (pin "B8") (pinfunction "SBU2_B8") (pintype "passive"))
    )
    (net (code "64") (name "unconnected-(X1-TX1+-PadA2)") (class "Default")
      (node (ref "X1") (pin "A2") (pinfunction "TX1+_A2") (pintype "passive"))
    )
    (net (code "65") (name "unconnected-(X1-TX1--PadA3)") (class "Default")
      (node (ref "X1") (pin "A3") (pinfunction "TX1-_A3") (pintype "passive"))
    )
    (net (code "66") (name "unconnected-(X1-TX2+-PadB2)") (class "Default")
      (node (ref "X1") (pin "B2") (pinfunction "TX2+_B2") (pintype "passive"))
    )
    (net (code "67") (name "unconnected-(X1-TX2--PadB3)") (class "Default")
      (node (ref "X1") (pin "B3") (pinfunction "TX2-_B3") (pintype "passive"))
    )
  )
)
